# GPIO_pins.net
KiCad netlist of a schematic drawn in EAGLE
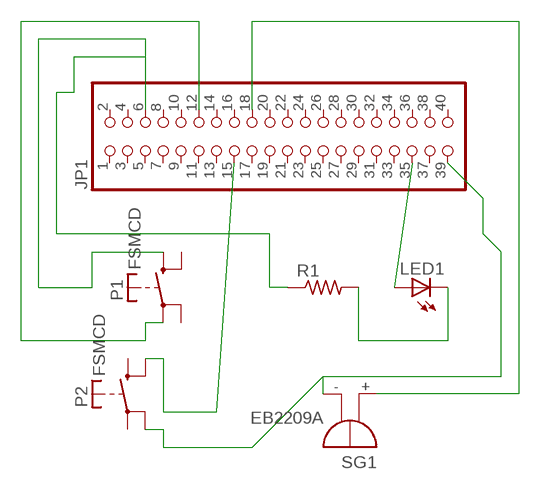
[diagram p0: schematic, sheet 1]

(export (version "E")
  (design (tool "Eeschema 10.0.6"))
  (components
    (comp (ref "JP1")
      (value "PINHD-2X20")
      (footprint "eagle-import:2X20")
      (libsource (lib "eagle-import") (part "PINHD-2X20"))
    )
    (comp (ref "LED1")
      (value "LED5MM")
      (footprint "eagle-import:LED5MM")
      (libsource (lib "eagle-import") (part "LED5MM"))
    )
    (comp (ref "P1")
      (value "FSMCD")
      (footprint "eagle-import:FSMCD")
      (libsource (lib "eagle-import") (part "FSMCD"))
    )
    (comp (ref "P2")
      (value "FSMCD")
      (footprint "eagle-import:FSMCD")
      (libsource (lib "eagle-import") (part "FSMCD"))
    )
    (comp (ref "R1")
      (value "R-US_0207/5V")
      (footprint "eagle-import:0207_5V")
      (libsource (lib "eagle-import") (part "R-US_0207/5V"))
    )
    (comp (ref "SG1")
      (value "EB2209A")
      (footprint "eagle-import:EB2209A")
      (libsource (lib "eagle-import") (part "EB2209A"))
    )
  )
  (nets
    (net (code "1") (name "Net-(JP1-Pad6)") (class "Default")
      (node (ref "JP1") (pin "6") (pinfunction "6_6") (pintype "passive"))
      (node (ref "P1") (pin "P$3") (pinfunction "S_P$3") (pintype "passive"))
      (node (ref "R1") (pin "1") (pinfunction "1_1") (pintype "passive"))
    )
    (net (code "2") (name "Net-(JP1-Pad12)") (class "Default")
      (node (ref "JP1") (pin "12") (pinfunction "12_12") (pintype "passive"))
      (node (ref "P1") (pin "P$1") (pinfunction "P_P$1") (pintype "passive"))
    )
    (net (code "3") (name "Net-(JP1-Pad15)") (class "Default")
      (node (ref "JP1") (pin "15") (pinfunction "15_15") (pintype "passive"))
      (node (ref "P2") (pin "P$4") (pinfunction "S_P$4") (pintype "passive"))
    )
    (net (code "4") (name "Net-(JP1-Pad18)") (class "Default")
      (node (ref "JP1") (pin "18") (pinfunction "18_18") (pintype "passive"))
      (node (ref "SG1") (pin "+") (pinfunction "+_+") (pintype "passive"))
    )
    (net (code "5") (name "Net-(JP1-Pad35)") (class "Default")
      (node (ref "JP1") (pin "35") (pinfunction "35_35") (pintype "passive"))
      (node (ref "LED1") (pin "A") (pinfunction "A_A") (pintype "passive"))
    )
    (net (code "6") (name "Net-(JP1-Pad39)") (class "Default")
      (node (ref "JP1") (pin "39") (pinfunction "39_39") (pintype "passive"))
      (node (ref "P2") (pin "P$2") (pinfunction "P_P$2") (pintype "passive"))
      (node (ref "SG1") (pin "-") (pinfunction "-_-") (pintype "passive"))
    )
    (net (code "7") (name "Net-(LED1-C)") (class "Default")
      (node (ref "LED1") (pin "K") (pinfunction "C_K") (pintype "passive"))
      (node (ref "R1") (pin "2") (pinfunction "2_2") (pintype "passive"))
    )
    (net (code "8") (name "unconnected-(JP1-Pad1)") (class "Default")
      (node (ref "JP1") (pin "1") (pinfunction "1_1") (pintype "passive"))
    )
    (net (code "9") (name "unconnected-(JP1-Pad2)") (class "Default")
      (node (ref "JP1") (pin "2") (pinfunction "2_2") (pintype "passive"))
    )
    (net (code "10") (name "unconnected-(JP1-Pad3)") (class "Default")
      (node (ref "JP1") (pin "3") (pinfunction "3_3") (pintype "passive"))
    )
    (net (code "11") (name "unconnected-(JP1-Pad4)") (class "Default")
      (node (ref "JP1") (pin "4") (pinfunction "4_4") (pintype "passive"))
    )
    (net (code "12") (name "unconnected-(JP1-Pad5)") (class "Default")
      (node (ref "JP1") (pin "5") (pinfunction "5_5") (pintype "passive"))
    )
    (net (code "13") (name "unconnected-(JP1-Pad7)") (class "Default")
      (node (ref "JP1") (pin "7") (pinfunction "7_7") (pintype "passive"))
    )
    (net (code "14") (name "unconnected-(JP1-Pad8)") (class "Default")
      (node (ref "JP1") (pin "8") (pinfunction "8_8") (pintype "passive"))
    )
    (net (code "15") (name "unconnected-(JP1-Pad9)") (class "Default")
      (node (ref "JP1") (pin "9") (pinfunction "9_9") (pintype "passive"))
    )
    (net (code "16") (name "unconnected-(JP1-Pad10)") (class "Default")
      (node (ref "JP1") (pin "10") (pinfunction "10_10") (pintype "passive"))
    )
    (net (code "17") (name "unconnected-(JP1-Pad11)") (class "Default")
      (node (ref "JP1") (pin "11") (pinfunction "11_11") (pintype "passive"))
    )
    (net (code "18") (name "unconnected-(JP1-Pad13)") (class "Default")
      (node (ref "JP1") (pin "13") (pinfunction "13_13") (pintype "passive"))
    )
    (net (code "19") (name "unconnected-(JP1-Pad14)") (class "Default")
      (node (ref "JP1") (pin "14") (pinfunction "14_14") (pintype "passive"))
    )
    (net (code "20") (name "unconnected-(JP1-Pad16)") (class "Default")
      (node (ref "JP1") (pin "16") (pinfunction "16_16") (pintype "passive"))
    )
    (net (code "21") (name "unconnected-(JP1-Pad17)") (class "Default")
      (node (ref "JP1") (pin "17") (pinfunction "17_17") (pintype "passive"))
    )
    (net (code "22") (name "unconnected-(JP1-Pad19)") (class "Default")
      (node (ref "JP1") (pin "19") (pinfunction "19_19") (pintype "passive"))
    )
    (net (code "23") (name "unconnected-(JP1-Pad20)") (class "Default")
      (node (ref "JP1") (pin "20") (pinfunction "20_20") (pintype "passive"))
    )
    (net (code "24") (name "unconnected-(JP1-Pad21)") (class "Default")
      (node (ref "JP1") (pin "21") (pinfunction "21_21") (pintype "passive"))
    )
    (net (code "25") (name "unconnected-(JP1-Pad22)") (class "Default")
      (node (ref "JP1") (pin "22") (pinfunction "22_22") (pintype "passive"))
    )
    (net (code "26") (name "unconnected-(JP1-Pad23)") (class "Default")
      (node (ref "JP1") (pin "23") (pinfunction "23_23") (pintype "passive"))
    )
    (net (code "27") (name "unconnected-(JP1-Pad24)") (class "Default")
      (node (ref "JP1") (pin "24") (pinfunction "24_24") (pintype "passive"))
    )
    (net (code "28") (name "unconnected-(JP1-Pad25)") (class "Default")
      (node (ref "JP1") (pin "25") (pinfunction "25_25") (pintype "passive"))
    )
    (net (code "29") (name "unconnected-(JP1-Pad26)") (class "Default")
      (node (ref "JP1") (pin "26") (pinfunction "26_26") (pintype "passive"))
    )
    (net (code "30") (name "unconnected-(JP1-Pad27)") (class "Default")
      (node (ref "JP1") (pin "27") (pinfunction "27_27") (pintype "passive"))
    )
    (net (code "31") (name "unconnected-(JP1-Pad28)") (class "Default")
      (node (ref "JP1") (pin "28") (pinfunction "28_28") (pintype "passive"))
    )
    (net (code "32") (name "unconnected-(JP1-Pad29)") (class "Default")
      (node (ref "JP1") (pin "29") (pinfunction "29_29") (pintype "passive"))
    )
    (net (code "33") (name "unconnected-(JP1-Pad30)") (class "Default")
      (node (ref "JP1") (pin "30") (pinfunction "30_30") (pintype "passive"))
    )
    (net (code "34") (name "unconnected-(JP1-Pad31)") (class "Default")
      (node (ref "JP1") (pin "31") (pinfunction "31_31") (pintype "passive"))
    )
    (net (code "35") (name "unconnected-(JP1-Pad32)") (class "Default")
      (node (ref "JP1") (pin "32") (pinfunction "32_32") (pintype "passive"))
    )
    (net (code "36") (name "unconnected-(JP1-Pad33)") (class "Default")
      (node (ref "JP1") (pin "33") (pinfunction "33_33") (pintype "passive"))
    )
    (net (code "37") (name "unconnected-(JP1-Pad34)") (class "Default")
      (node (ref "JP1") (pin "34") (pinfunction "34_34") (pintype "passive"))
    )
    (net (code "38") (name "unconnected-(JP1-Pad36)") (class "Default")
      (node (ref "JP1") (pin "36") (pinfunction "36_36") (pintype "passive"))
    )
    (net (code "39") (name "unconnected-(JP1-Pad37)") (class "Default")
      (node (ref "JP1") (pin "37") (pinfunction "37_37") (pintype "passive"))
    )
    (net (code "40") (name "unconnected-(JP1-Pad38)") (class "Default")
      (node (ref "JP1") (pin "38") (pinfunction "38_38") (pintype "passive"))
    )
    (net (code "41") (name "unconnected-(JP1-Pad40)") (class "Default")
      (node (ref "JP1") (pin "40") (pinfunction "40_40") (pintype "passive"))
    )
    (net (code "42") (name "unconnected-(P1-P-PadP$2)") (class "Default")
      (node (ref "P1") (pin "P$2") (pinfunction "P_P$2") (pintype "passive"))
    )
    (net (code "43") (name "unconnected-(P1-S-PadP$4)") (class "Default")
      (node (ref "P1") (pin "P$4") (pinfunction "S_P$4") (pintype "passive"))
    )
    (net (code "44") (name "unconnected-(P2-P-PadP$1)") (class "Default")
      (node (ref "P2") (pin "P$1") (pinfunction "P_P$1") (pintype "passive"))
    )
    (net (code "45") (name "unconnected-(P2-S-PadP$3)") (class "Default")
      (node (ref "P2") (pin "P$3") (pinfunction "S_P$3") (pintype "passive"))
    )
  )
)
